# cpuledin.net
KiCad netlist of a schematic drawn in Altium Designer
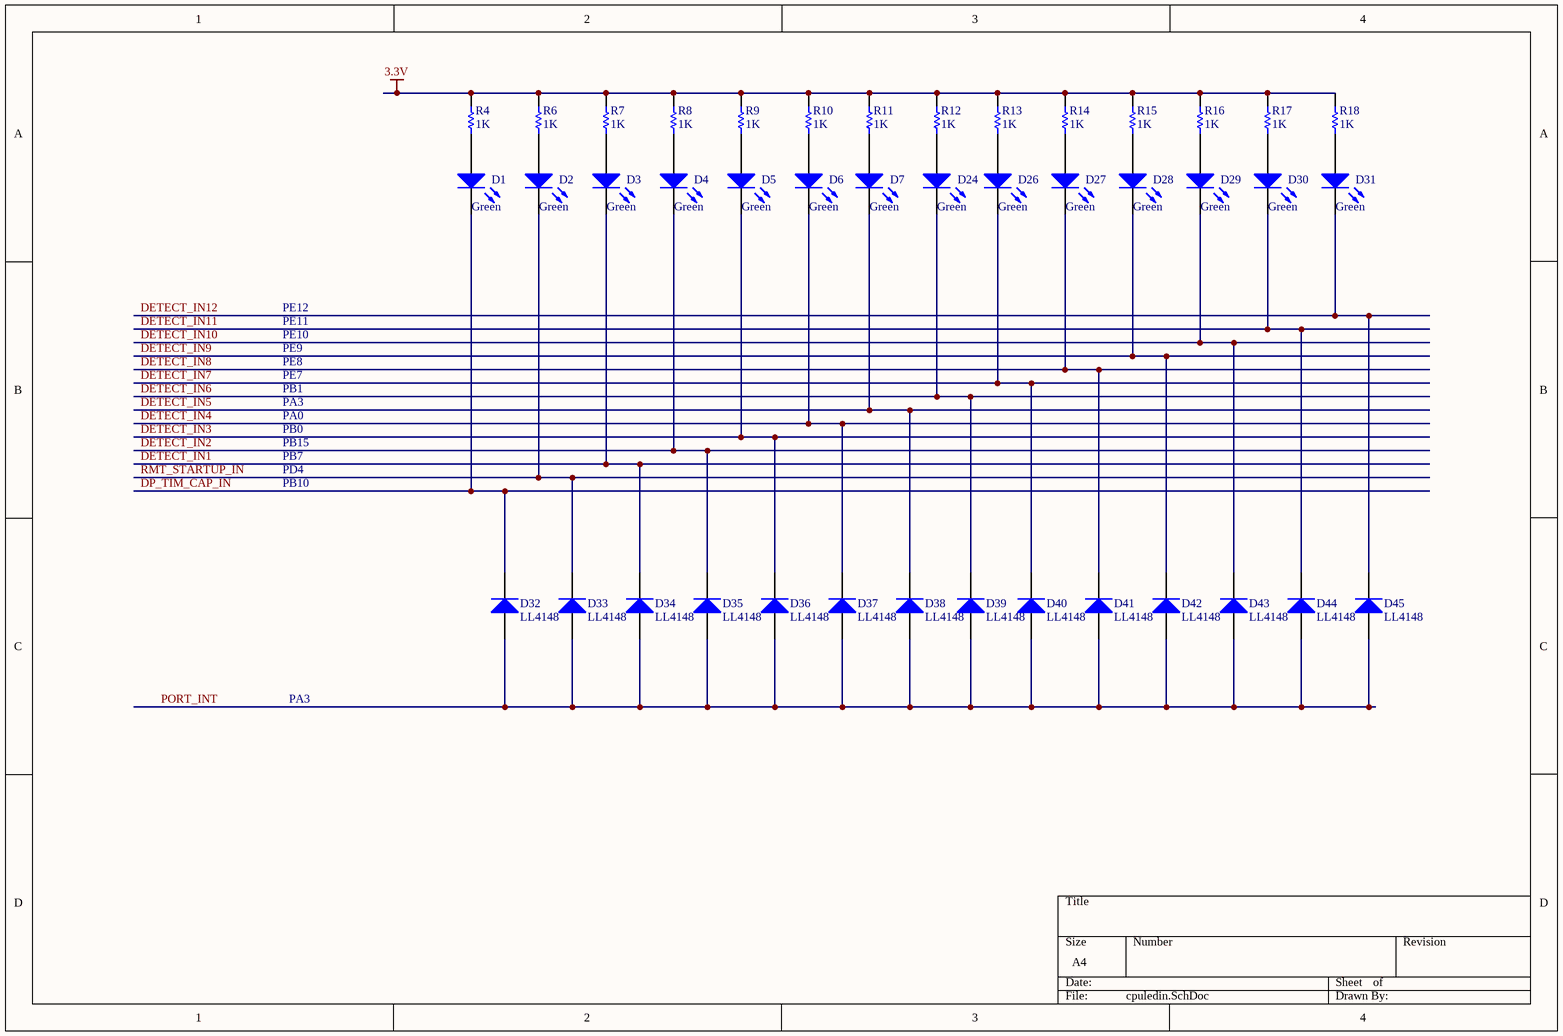
[diagram p0: cpuledin.SchDoc]

(export (version "E")
  (design (tool "Eeschema 10.0.6"))
  (components
    (comp (ref "D1")
      (value "Green")
      (footprint "CD2012-0805")
      (description "Green LED,Output indicate.")
      (fields (field (name "PUBLISHER") "Altium Limited"))
      (libsource (lib "Miscellaneous Devices") (part "LED1"))
    )
    (comp (ref "D2")
      (value "Green")
      (footprint "CD2012-0805")
      (description "Green LED,Output indicate.")
      (fields (field (name "PUBLISHER") "Altium Limited"))
      (libsource (lib "Miscellaneous Devices") (part "LED1"))
    )
    (comp (ref "D3")
      (value "Green")
      (footprint "CD2012-0805")
      (description "Green LED,Output indicate.")
      (fields (field (name "PUBLISHER") "Altium Limited"))
      (libsource (lib "Miscellaneous Devices") (part "LED1"))
    )
    (comp (ref "D4")
      (value "Green")
      (footprint "CD2012-0805")
      (description "Green LED,Output indicate.")
      (fields (field (name "PUBLISHER") "Altium Limited"))
      (libsource (lib "Miscellaneous Devices") (part "LED1"))
    )
    (comp (ref "D5")
      (value "Green")
      (footprint "CD2012-0805")
      (description "Green LED,Output indicate.")
      (fields (field (name "PUBLISHER") "Altium Limited"))
      (libsource (lib "Miscellaneous Devices") (part "LED1"))
    )
    (comp (ref "D6")
      (value "Green")
      (footprint "CD2012-0805")
      (description "Green LED,Output indicate.")
      (fields (field (name "PUBLISHER") "Altium Limited"))
      (libsource (lib "Miscellaneous Devices") (part "LED1"))
    )
    (comp (ref "D7")
      (value "Green")
      (footprint "CD2012-0805")
      (description "Green LED,Output indicate.")
      (fields (field (name "PUBLISHER") "Altium Limited"))
      (libsource (lib "Miscellaneous Devices") (part "LED1"))
    )
    (comp (ref "D24")
      (value "Green")
      (footprint "CD2012-0805")
      (description "Green LED,Output indicate.")
      (fields (field (name "PUBLISHER") "Altium Limited"))
      (libsource (lib "Miscellaneous Devices") (part "LED1"))
    )
    (comp (ref "D26")
      (value "Green")
      (footprint "CD2012-0805")
      (description "Green LED,Output indicate.")
      (fields (field (name "PUBLISHER") "Altium Limited"))
      (libsource (lib "Miscellaneous Devices") (part "LED1"))
    )
    (comp (ref "D27")
      (value "Green")
      (footprint "CD2012-0805")
      (description "Green LED,Output indicate.")
      (fields (field (name "PUBLISHER") "Altium Limited"))
      (libsource (lib "Miscellaneous Devices") (part "LED1"))
    )
    (comp (ref "D28")
      (value "Green")
      (footprint "CD2012-0805")
      (description "Green LED,Output indicate.")
      (fields (field (name "PUBLISHER") "Altium Limited"))
      (libsource (lib "Miscellaneous Devices") (part "LED1"))
    )
    (comp (ref "D29")
      (value "Green")
      (footprint "CD2012-0805")
      (description "Green LED,Output indicate.")
      (fields (field (name "PUBLISHER") "Altium Limited"))
      (libsource (lib "Miscellaneous Devices") (part "LED1"))
    )
    (comp (ref "D30")
      (value "Green")
      (footprint "CD2012-0805")
      (description "Green LED,Output indicate.")
      (fields (field (name "PUBLISHER") "Altium Limited"))
      (libsource (lib "Miscellaneous Devices") (part "LED1"))
    )
    (comp (ref "D31")
      (value "Green")
      (footprint "CD2012-0805")
      (description "Green LED,Output indicate.")
      (fields (field (name "PUBLISHER") "Altium Limited"))
      (libsource (lib "Miscellaneous Devices") (part "LED1"))
    )
    (comp (ref "D32")
      (value "LL4148")
      (footprint "CD2012-0805")
      (description "1 Amp General Purpose Rectifier")
      (fields (field (name "PUBLISHER") "Altium Limited"))
      (libsource (lib "Miscellaneous Devices") (part "Diode 1N4007"))
    )
    (comp (ref "D33")
      (value "LL4148")
      (footprint "CD2012-0805")
      (description "1 Amp General Purpose Rectifier")
      (fields (field (name "PUBLISHER") "Altium Limited"))
      (libsource (lib "Miscellaneous Devices") (part "Diode 1N4007"))
    )
    (comp (ref "D34")
      (value "LL4148")
      (footprint "CD2012-0805")
      (description "1 Amp General Purpose Rectifier")
      (fields (field (name "PUBLISHER") "Altium Limited"))
      (libsource (lib "Miscellaneous Devices") (part "Diode 1N4007"))
    )
    (comp (ref "D35")
      (value "LL4148")
      (footprint "CD2012-0805")
      (description "1 Amp General Purpose Rectifier")
      (fields (field (name "PUBLISHER") "Altium Limited"))
      (libsource (lib "Miscellaneous Devices") (part "Diode 1N4007"))
    )
    (comp (ref "D36")
      (value "LL4148")
      (footprint "CD2012-0805")
      (description "1 Amp General Purpose Rectifier")
      (fields (field (name "PUBLISHER") "Altium Limited"))
      (libsource (lib "Miscellaneous Devices") (part "Diode 1N4007"))
    )
    (comp (ref "D37")
      (value "LL4148")
      (footprint "CD2012-0805")
      (description "1 Amp General Purpose Rectifier")
      (fields (field (name "PUBLISHER") "Altium Limited"))
      (libsource (lib "Miscellaneous Devices") (part "Diode 1N4007"))
    )
    (comp (ref "D38")
      (value "LL4148")
      (footprint "CD2012-0805")
      (description "1 Amp General Purpose Rectifier")
      (fields (field (name "PUBLISHER") "Altium Limited"))
      (libsource (lib "Miscellaneous Devices") (part "Diode 1N4007"))
    )
    (comp (ref "D39")
      (value "LL4148")
      (footprint "CD2012-0805")
      (description "1 Amp General Purpose Rectifier")
      (fields (field (name "PUBLISHER") "Altium Limited"))
      (libsource (lib "Miscellaneous Devices") (part "Diode 1N4007"))
    )
    (comp (ref "D40")
      (value "LL4148")
      (footprint "CD2012-0805")
      (description "1 Amp General Purpose Rectifier")
      (fields (field (name "PUBLISHER") "Altium Limited"))
      (libsource (lib "Miscellaneous Devices") (part "Diode 1N4007"))
    )
    (comp (ref "D41")
      (value "LL4148")
      (footprint "CD2012-0805")
      (description "1 Amp General Purpose Rectifier")
      (fields (field (name "PUBLISHER") "Altium Limited"))
      (libsource (lib "Miscellaneous Devices") (part "Diode 1N4007"))
    )
    (comp (ref "D42")
      (value "LL4148")
      (footprint "CD2012-0805")
      (description "1 Amp General Purpose Rectifier")
      (fields (field (name "PUBLISHER") "Altium Limited"))
      (libsource (lib "Miscellaneous Devices") (part "Diode 1N4007"))
    )
    (comp (ref "D43")
      (value "LL4148")
      (footprint "CD2012-0805")
      (description "1 Amp General Purpose Rectifier")
      (fields (field (name "PUBLISHER") "Altium Limited"))
      (libsource (lib "Miscellaneous Devices") (part "Diode 1N4007"))
    )
    (comp (ref "D44")
      (value "LL4148")
      (footprint "CD2012-0805")
      (description "1 Amp General Purpose Rectifier")
      (fields (field (name "PUBLISHER") "Altium Limited"))
      (libsource (lib "Miscellaneous Devices") (part "Diode 1N4007"))
    )
    (comp (ref "D45")
      (value "LL4148")
      (footprint "CD2012-0805")
      (description "1 Amp General Purpose Rectifier")
      (fields (field (name "PUBLISHER") "Altium Limited"))
      (libsource (lib "Miscellaneous Devices") (part "Diode 1N4007"))
    )
    (comp (ref "R4")
      (value "1K")
      (footprint "RESC2012M")
      (description "Resistor")
      (fields (field (name "PUBLISHER") "Altium Limited"))
      (libsource (lib "Miscellaneous Devices") (part "Res1"))
    )
    (comp (ref "R6")
      (value "1K")
      (footprint "RESC2012M")
      (description "Resistor")
      (fields (field (name "PUBLISHER") "Altium Limited"))
      (libsource (lib "Miscellaneous Devices") (part "Res1"))
    )
    (comp (ref "R7")
      (value "1K")
      (footprint "RESC2012M")
      (description "Resistor")
      (fields (field (name "PUBLISHER") "Altium Limited"))
      (libsource (lib "Miscellaneous Devices") (part "Res1"))
    )
    (comp (ref "R8")
      (value "1K")
      (footprint "RESC2012M")
      (description "Resistor")
      (fields (field (name "PUBLISHER") "Altium Limited"))
      (libsource (lib "Miscellaneous Devices") (part "Res1"))
    )
    (comp (ref "R9")
      (value "1K")
      (footprint "RESC2012M")
      (description "Resistor")
      (fields (field (name "PUBLISHER") "Altium Limited"))
      (libsource (lib "Miscellaneous Devices") (part "Res1"))
    )
    (comp (ref "R10")
      (value "1K")
      (footprint "RESC2012M")
      (description "Resistor")
      (fields (field (name "PUBLISHER") "Altium Limited"))
      (libsource (lib "Miscellaneous Devices") (part "Res1"))
    )
    (comp (ref "R11")
      (value "1K")
      (footprint "RESC2012M")
      (description "Resistor")
      (fields (field (name "PUBLISHER") "Altium Limited"))
      (libsource (lib "Miscellaneous Devices") (part "Res1"))
    )
    (comp (ref "R12")
      (value "1K")
      (footprint "RESC2012M")
      (description "Resistor")
      (fields (field (name "PUBLISHER") "Altium Limited"))
      (libsource (lib "Miscellaneous Devices") (part "Res1"))
    )
    (comp (ref "R13")
      (value "1K")
      (footprint "RESC2012M")
      (description "Resistor")
      (fields (field (name "PUBLISHER") "Altium Limited"))
      (libsource (lib "Miscellaneous Devices") (part "Res1"))
    )
    (comp (ref "R14")
      (value "1K")
      (footprint "RESC2012M")
      (description "Resistor")
      (fields (field (name "PUBLISHER") "Altium Limited"))
      (libsource (lib "Miscellaneous Devices") (part "Res1"))
    )
    (comp (ref "R15")
      (value "1K")
      (footprint "RESC2012M")
      (description "Resistor")
      (fields (field (name "PUBLISHER") "Altium Limited"))
      (libsource (lib "Miscellaneous Devices") (part "Res1"))
    )
    (comp (ref "R16")
      (value "1K")
      (footprint "RESC2012M")
      (description "Resistor")
      (fields (field (name "PUBLISHER") "Altium Limited"))
      (libsource (lib "Miscellaneous Devices") (part "Res1"))
    )
    (comp (ref "R17")
      (value "1K")
      (footprint "RESC2012M")
      (description "Resistor")
      (fields (field (name "PUBLISHER") "Altium Limited"))
      (libsource (lib "Miscellaneous Devices") (part "Res1"))
    )
    (comp (ref "R18")
      (value "1K")
      (footprint "RESC2012M")
      (description "Resistor")
      (fields (field (name "PUBLISHER") "Altium Limited"))
      (libsource (lib "Miscellaneous Devices") (part "Res1"))
    )
  )
  (nets
    (net (code "1") (name "/DETECT_IN1") (class "Default")
      (node (ref "D3") (pin "2") (pinfunction "K_2") (pintype "passive"))
      (node (ref "D34") (pin "2") (pinfunction "K_2") (pintype "passive"))
    )
    (net (code "2") (name "/DETECT_IN2") (class "Default")
      (node (ref "D35") (pin "2") (pinfunction "K_2") (pintype "passive"))
      (node (ref "D4") (pin "2") (pinfunction "K_2") (pintype "passive"))
    )
    (net (code "3") (name "/DETECT_IN3") (class "Default")
      (node (ref "D36") (pin "2") (pinfunction "K_2") (pintype "passive"))
      (node (ref "D5") (pin "2") (pinfunction "K_2") (pintype "passive"))
    )
    (net (code "4") (name "/DETECT_IN4") (class "Default")
      (node (ref "D37") (pin "2") (pinfunction "K_2") (pintype "passive"))
      (node (ref "D6") (pin "2") (pinfunction "K_2") (pintype "passive"))
    )
    (net (code "5") (name "/DETECT_IN5") (class "Default")
      (node (ref "D38") (pin "2") (pinfunction "K_2") (pintype "passive"))
      (node (ref "D7") (pin "2") (pinfunction "K_2") (pintype "passive"))
    )
    (net (code "6") (name "/DETECT_IN6") (class "Default")
      (node (ref "D24") (pin "2") (pinfunction "K_2") (pintype "passive"))
      (node (ref "D39") (pin "2") (pinfunction "K_2") (pintype "passive"))
    )
    (net (code "7") (name "/DETECT_IN7") (class "Default")
      (node (ref "D26") (pin "2") (pinfunction "K_2") (pintype "passive"))
      (node (ref "D40") (pin "2") (pinfunction "K_2") (pintype "passive"))
    )
    (net (code "8") (name "/DETECT_IN8") (class "Default")
      (node (ref "D27") (pin "2") (pinfunction "K_2") (pintype "passive"))
      (node (ref "D41") (pin "2") (pinfunction "K_2") (pintype "passive"))
    )
    (net (code "9") (name "/DETECT_IN9") (class "Default")
      (node (ref "D28") (pin "2") (pinfunction "K_2") (pintype "passive"))
      (node (ref "D42") (pin "2") (pinfunction "K_2") (pintype "passive"))
    )
    (net (code "10") (name "/DETECT_IN10") (class "Default")
      (node (ref "D29") (pin "2") (pinfunction "K_2") (pintype "passive"))
      (node (ref "D43") (pin "2") (pinfunction "K_2") (pintype "passive"))
    )
    (net (code "11") (name "/DETECT_IN11") (class "Default")
      (node (ref "D30") (pin "2") (pinfunction "K_2") (pintype "passive"))
      (node (ref "D44") (pin "2") (pinfunction "K_2") (pintype "passive"))
    )
    (net (code "12") (name "/DETECT_IN12") (class "Default")
      (node (ref "D31") (pin "2") (pinfunction "K_2") (pintype "passive"))
      (node (ref "D45") (pin "2") (pinfunction "K_2") (pintype "passive"))
    )
    (net (code "13") (name "/DP_TIM_CAP_IN") (class "Default")
      (node (ref "D1") (pin "2") (pinfunction "K_2") (pintype "passive"))
      (node (ref "D32") (pin "2") (pinfunction "K_2") (pintype "passive"))
    )
    (net (code "14") (name "/PORT_INT") (class "Default")
      (node (ref "D32") (pin "1") (pinfunction "A_1") (pintype "passive"))
      (node (ref "D33") (pin "1") (pinfunction "A_1") (pintype "passive"))
      (node (ref "D34") (pin "1") (pinfunction "A_1") (pintype "passive"))
      (node (ref "D35") (pin "1") (pinfunction "A_1") (pintype "passive"))
      (node (ref "D36") (pin "1") (pinfunction "A_1") (pintype "passive"))
      (node (ref "D37") (pin "1") (pinfunction "A_1") (pintype "passive"))
      (node (ref "D38") (pin "1") (pinfunction "A_1") (pintype "passive"))
      (node (ref "D39") (pin "1") (pinfunction "A_1") (pintype "passive"))
      (node (ref "D40") (pin "1") (pinfunction "A_1") (pintype "passive"))
      (node (ref "D41") (pin "1") (pinfunction "A_1") (pintype "passive"))
      (node (ref "D42") (pin "1") (pinfunction "A_1") (pintype "passive"))
      (node (ref "D43") (pin "1") (pinfunction "A_1") (pintype "passive"))
      (node (ref "D44") (pin "1") (pinfunction "A_1") (pintype "passive"))
      (node (ref "D45") (pin "1") (pinfunction "A_1") (pintype "passive"))
    )
    (net (code "15") (name "/RMT_STARTUP_IN") (class "Default")
      (node (ref "D2") (pin "2") (pinfunction "K_2") (pintype "passive"))
      (node (ref "D33") (pin "2") (pinfunction "K_2") (pintype "passive"))
    )
    (net (code "16") (name "3.3V") (class "Default")
      (node (ref "R10") (pin "2") (pinfunction "2_2") (pintype "passive"))
      (node (ref "R11") (pin "2") (pinfunction "2_2") (pintype "passive"))
      (node (ref "R12") (pin "2") (pinfunction "2_2") (pintype "passive"))
      (node (ref "R13") (pin "2") (pinfunction "2_2") (pintype "passive"))
      (node (ref "R14") (pin "2") (pinfunction "2_2") (pintype "passive"))
      (node (ref "R15") (pin "2") (pinfunction "2_2") (pintype "passive"))
      (node (ref "R16") (pin "2") (pinfunction "2_2") (pintype "passive"))
      (node (ref "R17") (pin "2") (pinfunction "2_2") (pintype "passive"))
      (node (ref "R18") (pin "2") (pinfunction "2_2") (pintype "passive"))
      (node (ref "R4") (pin "2") (pinfunction "2_2") (pintype "passive"))
      (node (ref "R6") (pin "2") (pinfunction "2_2") (pintype "passive"))
      (node (ref "R7") (pin "2") (pinfunction "2_2") (pintype "passive"))
      (node (ref "R8") (pin "2") (pinfunction "2_2") (pintype "passive"))
      (node (ref "R9") (pin "2") (pinfunction "2_2") (pintype "passive"))
    )
    (net (code "17") (name "Net-(D1-A)") (class "Default")
      (node (ref "D1") (pin "1") (pinfunction "A_1") (pintype "passive"))
      (node (ref "R4") (pin "1") (pinfunction "1_1") (pintype "passive"))
    )
    (net (code "18") (name "Net-(D2-A)") (class "Default")
      (node (ref "D2") (pin "1") (pinfunction "A_1") (pintype "passive"))
      (node (ref "R6") (pin "1") (pinfunction "1_1") (pintype "passive"))
    )
    (net (code "19") (name "Net-(D3-A)") (class "Default")
      (node (ref "D3") (pin "1") (pinfunction "A_1") (pintype "passive"))
      (node (ref "R7") (pin "1") (pinfunction "1_1") (pintype "passive"))
    )
    (net (code "20") (name "Net-(D4-A)") (class "Default")
      (node (ref "D4") (pin "1") (pinfunction "A_1") (pintype "passive"))
      (node (ref "R8") (pin "1") (pinfunction "1_1") (pintype "passive"))
    )
    (net (code "21") (name "Net-(D5-A)") (class "Default")
      (node (ref "D5") (pin "1") (pinfunction "A_1") (pintype "passive"))
      (node (ref "R9") (pin "1") (pinfunction "1_1") (pintype "passive"))
    )
    (net (code "22") (name "Net-(D6-A)") (class "Default")
      (node (ref "D6") (pin "1") (pinfunction "A_1") (pintype "passive"))
      (node (ref "R10") (pin "1") (pinfunction "1_1") (pintype "passive"))
    )
    (net (code "23") (name "Net-(D7-A)") (class "Default")
      (node (ref "D7") (pin "1") (pinfunction "A_1") (pintype "passive"))
      (node (ref "R11") (pin "1") (pinfunction "1_1") (pintype "passive"))
    )
    (net (code "24") (name "Net-(D24-A)") (class "Default")
      (node (ref "D24") (pin "1") (pinfunction "A_1") (pintype "passive"))
      (node (ref "R12") (pin "1") (pinfunction "1_1") (pintype "passive"))
    )
    (net (code "25") (name "Net-(D26-A)") (class "Default")
      (node (ref "D26") (pin "1") (pinfunction "A_1") (pintype "passive"))
      (node (ref "R13") (pin "1") (pinfunction "1_1") (pintype "passive"))
    )
    (net (code "26") (name "Net-(D27-A)") (class "Default")
      (node (ref "D27") (pin "1") (pinfunction "A_1") (pintype "passive"))
      (node (ref "R14") (pin "1") (pinfunction "1_1") (pintype "passive"))
    )
    (net (code "27") (name "Net-(D28-A)") (class "Default")
      (node (ref "D28") (pin "1") (pinfunction "A_1") (pintype "passive"))
      (node (ref "R15") (pin "1") (pinfunction "1_1") (pintype "passive"))
    )
    (net (code "28") (name "Net-(D29-A)") (class "Default")
      (node (ref "D29") (pin "1") (pinfunction "A_1") (pintype "passive"))
      (node (ref "R16") (pin "1") (pinfunction "1_1") (pintype "passive"))
    )
    (net (code "29") (name "Net-(D30-A)") (class "Default")
      (node (ref "D30") (pin "1") (pinfunction "A_1") (pintype "passive"))
      (node (ref "R17") (pin "1") (pinfunction "1_1") (pintype "passive"))
    )
    (net (code "30") (name "Net-(D31-A)") (class "Default")
      (node (ref "D31") (pin "1") (pinfunction "A_1") (pintype "passive"))
      (node (ref "R18") (pin "1") (pinfunction "1_1") (pintype "passive"))
    )
  )
)
